# display_v1.net
KiCad netlist of a schematic drawn in EAGLE
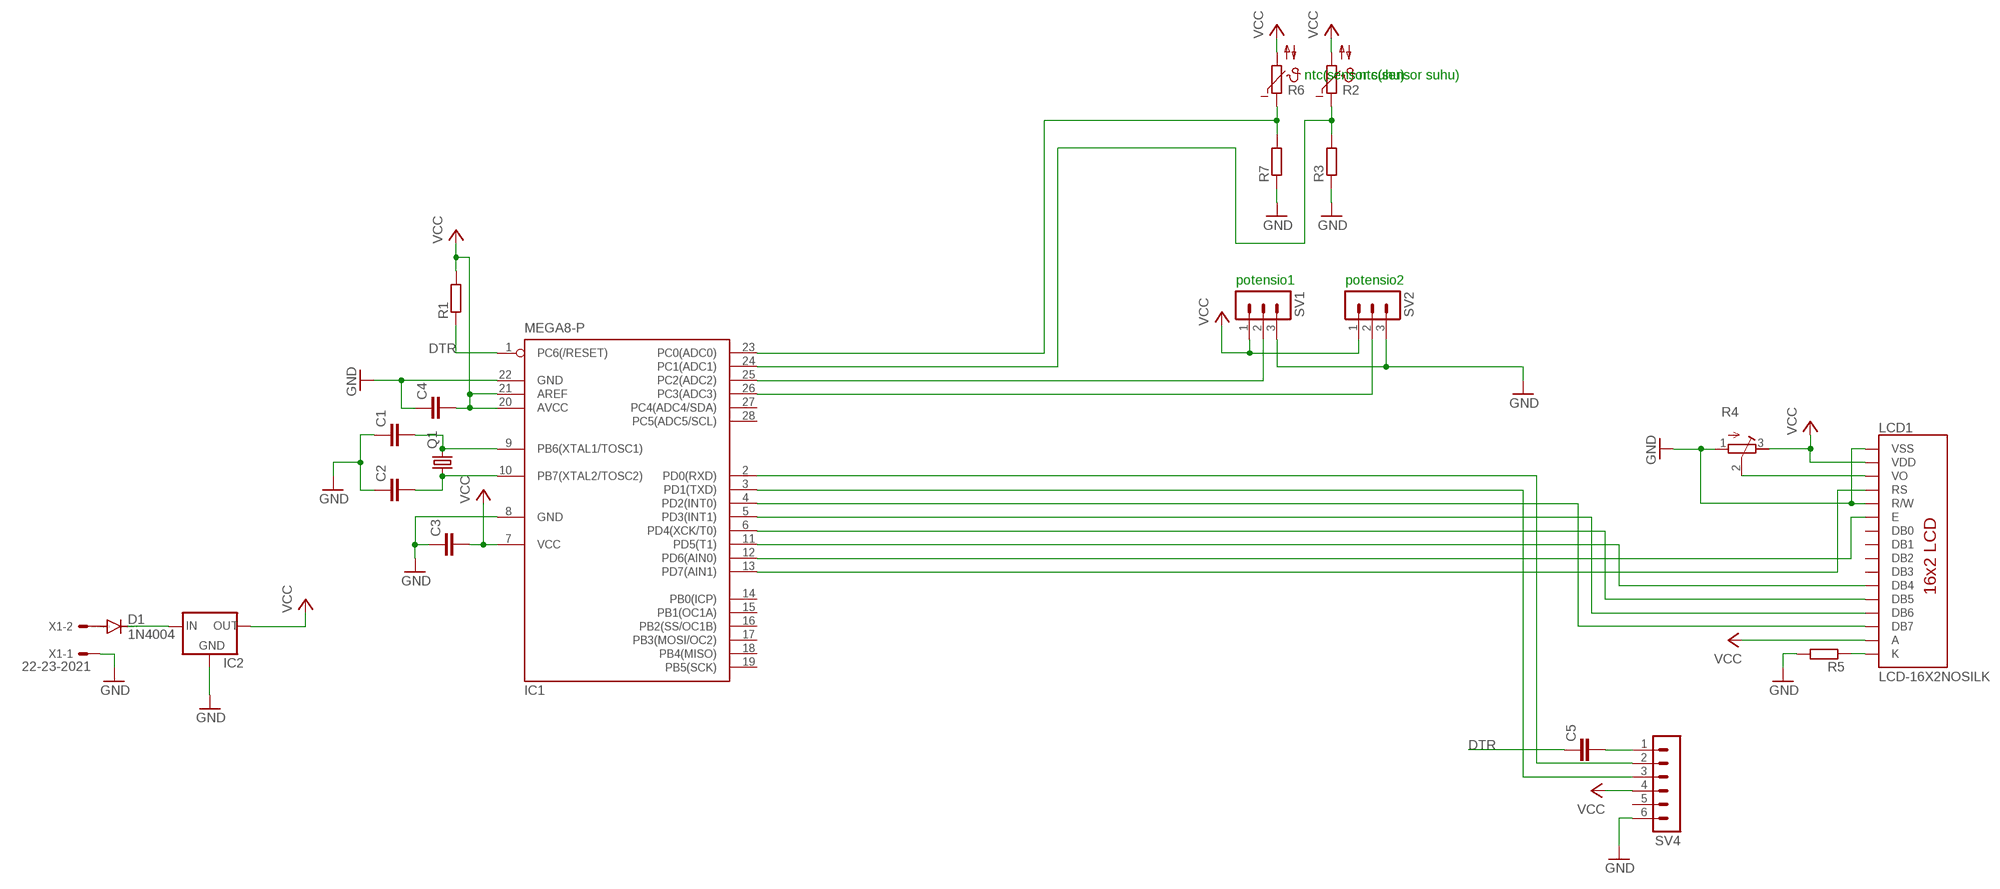
[diagram p0: schematic, sheet 1]

(export (version "E")
  (design (tool "Eeschema 10.0.6"))
  (components
    (comp (ref "C1")
      (value "C-EU025-025X050")
      (footprint "eagle-import:C025-025X050")
      (libsource (lib "eagle-import") (part "C-EU025-025X050"))
    )
    (comp (ref "C2")
      (value "C-EU025-025X050")
      (footprint "eagle-import:C025-025X050")
      (libsource (lib "eagle-import") (part "C-EU025-025X050"))
    )
    (comp (ref "C3")
      (value "C-EU050-025X075")
      (footprint "eagle-import:C050-025X075")
      (libsource (lib "eagle-import") (part "C-EU050-025X075"))
    )
    (comp (ref "C4")
      (value "C-EU050-025X075")
      (footprint "eagle-import:C050-025X075")
      (libsource (lib "eagle-import") (part "C-EU050-025X075"))
    )
    (comp (ref "C5")
      (value "C-EU050-025X075")
      (footprint "eagle-import:C050-025X075")
      (libsource (lib "eagle-import") (part "C-EU050-025X075"))
    )
    (comp (ref "D1")
      (value "1N4004")
      (footprint "eagle-import:DO41-10")
      (libsource (lib "eagle-import") (part "1N4004"))
    )
    (comp (ref "IC1")
      (value "MEGA8-P")
      (footprint "eagle-import:DIL28-3")
      (libsource (lib "eagle-import") (part "MEGA8-P"))
    )
    (comp (ref "IC2")
      (value "78XXL")
      (footprint "eagle-import:78XXL")
      (libsource (lib "eagle-import") (part "78XXL"))
    )
    (comp (ref "LCD1")
      (value "LCD-16X2NOSILK")
      (footprint "eagle-import:LCD-16X2_NOSILK")
      (libsource (lib "eagle-import") (part "LCD-16X2NOSILK"))
    )
    (comp (ref "Q1")
      (value "CRYSTALHC49S")
      (footprint "eagle-import:HC49_S")
      (libsource (lib "eagle-import") (part "CRYSTALHC49S"))
    )
    (comp (ref "R1")
      (value "R-EU_0204/7")
      (footprint "eagle-import:0204_7")
      (libsource (lib "eagle-import") (part "R-EU_0204/7"))
    )
    (comp (ref "R2")
      (value "NTC642-6")
      (footprint "eagle-import:P642")
      (libsource (lib "eagle-import") (part "NTC642-6"))
    )
    (comp (ref "R3")
      (value "R-EU_0204/7")
      (footprint "eagle-import:0204_7")
      (libsource (lib "eagle-import") (part "R-EU_0204/7"))
    )
    (comp (ref "R4")
      (value "R-TRIMM64W")
      (footprint "eagle-import:RTRIM64W")
      (libsource (lib "eagle-import") (part "R-TRIMM64W"))
    )
    (comp (ref "R5")
      (value "R-EU_0204/7")
      (footprint "eagle-import:0204_7")
      (libsource (lib "eagle-import") (part "R-EU_0204/7"))
    )
    (comp (ref "R6")
      (value "NTC642-6")
      (footprint "eagle-import:P642")
      (libsource (lib "eagle-import") (part "NTC642-6"))
    )
    (comp (ref "R7")
      (value "R-EU_0204/7")
      (footprint "eagle-import:0204_7")
      (libsource (lib "eagle-import") (part "R-EU_0204/7"))
    )
    (comp (ref "SV1")
      (value "MA03-1")
      (footprint "eagle-import:MA03-1")
      (libsource (lib "eagle-import") (part "MA03-1"))
    )
    (comp (ref "SV2")
      (value "MA03-1")
      (footprint "eagle-import:MA03-1")
      (libsource (lib "eagle-import") (part "MA03-1"))
    )
    (comp (ref "SV4")
      (value "MA06-1")
      (footprint "eagle-import:MA06-1")
      (libsource (lib "eagle-import") (part "MA06-1"))
    )
    (comp (ref "X1")
      (value "22-23-2021")
      (footprint "eagle-import:22-23-2021")
      (fields (field (name "MF") "MOLEX"))
      (libsource (lib "eagle-import") (part "22-23-2021"))
    )
  )
  (nets
    (net (code "1") (name "/DTR") (class "Default")
      (node (ref "C5") (pin "1") (pinfunction "1_1") (pintype "passive"))
      (node (ref "IC1") (pin "1") (pinfunction "PC6(/RESET)_1") (pintype "bidirectional"))
      (node (ref "R1") (pin "1") (pinfunction "1_1") (pintype "passive"))
    )
    (net (code "2") (name "GND") (class "Default")
      (node (ref "C1") (pin "1") (pinfunction "1_1") (pintype "passive"))
      (node (ref "C2") (pin "1") (pinfunction "1_1") (pintype "passive"))
      (node (ref "C3") (pin "1") (pinfunction "1_1") (pintype "passive"))
      (node (ref "C4") (pin "1") (pinfunction "1_1") (pintype "passive"))
      (node (ref "IC1") (pin "22") (pinfunction "GND_22") (pintype "power_in"))
      (node (ref "IC1") (pin "8") (pinfunction "GND_8") (pintype "power_in"))
      (node (ref "IC2") (pin "GND") (pinfunction "GND_GND") (pintype "input"))
      (node (ref "LCD1") (pin "1") (pinfunction "VSS_1") (pintype "power_in"))
      (node (ref "LCD1") (pin "5") (pinfunction "R/W_5") (pintype "input"))
      (node (ref "R3") (pin "1") (pinfunction "1_1") (pintype "passive"))
      (node (ref "R4") (pin "1") (pinfunction "A_1") (pintype "passive"))
      (node (ref "R5") (pin "2") (pinfunction "2_2") (pintype "passive"))
      (node (ref "R7") (pin "1") (pinfunction "1_1") (pintype "passive"))
      (node (ref "SV1") (pin "3") (pinfunction "3_3") (pintype "passive"))
      (node (ref "SV2") (pin "3") (pinfunction "3_3") (pintype "passive"))
      (node (ref "SV4") (pin "6") (pinfunction "6_6") (pintype "passive"))
      (node (ref "X1") (pin "1") (pinfunction "S_1") (pintype "passive"))
    )
    (net (code "3") (name "Net-(C5-Pad2)") (class "Default")
      (node (ref "C5") (pin "2") (pinfunction "2_2") (pintype "passive"))
      (node (ref "SV4") (pin "1") (pinfunction "1_1") (pintype "passive"))
    )
    (net (code "4") (name "Net-(D1-PadC)") (class "Default")
      (node (ref "D1") (pin "C") (pinfunction "C_C") (pintype "passive"))
      (node (ref "IC2") (pin "IN") (pinfunction "IN_IN") (pintype "input"))
    )
    (net (code "5") (name "Net-(IC1-PB6(XTAL1{slash}TOSC1))") (class "Default")
      (node (ref "C1") (pin "2") (pinfunction "2_2") (pintype "passive"))
      (node (ref "IC1") (pin "9") (pinfunction "PB6(XTAL1/TOSC1)_9") (pintype "bidirectional"))
      (node (ref "Q1") (pin "2") (pinfunction "2_2") (pintype "passive"))
    )
    (net (code "6") (name "Net-(IC1-PB7(XTAL2{slash}TOSC2))") (class "Default")
      (node (ref "C2") (pin "2") (pinfunction "2_2") (pintype "passive"))
      (node (ref "IC1") (pin "10") (pinfunction "PB7(XTAL2/TOSC2)_10") (pintype "bidirectional"))
      (node (ref "Q1") (pin "1") (pinfunction "1_1") (pintype "passive"))
    )
    (net (code "7") (name "Net-(IC1-PC0(ADC0))") (class "Default")
      (node (ref "IC1") (pin "23") (pinfunction "PC0(ADC0)_23") (pintype "bidirectional"))
      (node (ref "R6") (pin "1") (pinfunction "1_1") (pintype "passive"))
      (node (ref "R7") (pin "2") (pinfunction "2_2") (pintype "passive"))
    )
    (net (code "8") (name "Net-(IC1-PC1(ADC1))") (class "Default")
      (node (ref "IC1") (pin "24") (pinfunction "PC1(ADC1)_24") (pintype "bidirectional"))
      (node (ref "R2") (pin "1") (pinfunction "1_1") (pintype "passive"))
      (node (ref "R3") (pin "2") (pinfunction "2_2") (pintype "passive"))
    )
    (net (code "9") (name "Net-(IC1-PC2(ADC2))") (class "Default")
      (node (ref "IC1") (pin "25") (pinfunction "PC2(ADC2)_25") (pintype "bidirectional"))
      (node (ref "SV1") (pin "2") (pinfunction "2_2") (pintype "passive"))
    )
    (net (code "10") (name "Net-(IC1-PC3(ADC3))") (class "Default")
      (node (ref "IC1") (pin "26") (pinfunction "PC3(ADC3)_26") (pintype "bidirectional"))
      (node (ref "SV2") (pin "2") (pinfunction "2_2") (pintype "passive"))
    )
    (net (code "11") (name "Net-(IC1-PD0(RXD))") (class "Default")
      (node (ref "IC1") (pin "2") (pinfunction "PD0(RXD)_2") (pintype "bidirectional"))
      (node (ref "SV4") (pin "2") (pinfunction "2_2") (pintype "passive"))
    )
    (net (code "12") (name "Net-(IC1-PD1(TXD))") (class "Default")
      (node (ref "IC1") (pin "3") (pinfunction "PD1(TXD)_3") (pintype "bidirectional"))
      (node (ref "SV4") (pin "3") (pinfunction "3_3") (pintype "passive"))
    )
    (net (code "13") (name "Net-(IC1-PD2(INT0))") (class "Default")
      (node (ref "IC1") (pin "4") (pinfunction "PD2(INT0)_4") (pintype "bidirectional"))
      (node (ref "LCD1") (pin "14") (pinfunction "DB7_14") (pintype "bidirectional"))
    )
    (net (code "14") (name "Net-(IC1-PD3(INT1))") (class "Default")
      (node (ref "IC1") (pin "5") (pinfunction "PD3(INT1)_5") (pintype "bidirectional"))
      (node (ref "LCD1") (pin "13") (pinfunction "DB6_13") (pintype "bidirectional"))
    )
    (net (code "15") (name "Net-(IC1-PD4(XCK{slash}T0))") (class "Default")
      (node (ref "IC1") (pin "6") (pinfunction "PD4(XCK/T0)_6") (pintype "bidirectional"))
      (node (ref "LCD1") (pin "12") (pinfunction "DB5_12") (pintype "bidirectional"))
    )
    (net (code "16") (name "Net-(IC1-PD5(T1))") (class "Default")
      (node (ref "IC1") (pin "11") (pinfunction "PD5(T1)_11") (pintype "bidirectional"))
      (node (ref "LCD1") (pin "11") (pinfunction "DB4_11") (pintype "bidirectional"))
    )
    (net (code "17") (name "Net-(IC1-PD6(AIN0))") (class "Default")
      (node (ref "IC1") (pin "12") (pinfunction "PD6(AIN0)_12") (pintype "bidirectional"))
      (node (ref "LCD1") (pin "6") (pinfunction "E_6") (pintype "input"))
    )
    (net (code "18") (name "Net-(IC1-PD7(AIN1))") (class "Default")
      (node (ref "IC1") (pin "13") (pinfunction "PD7(AIN1)_13") (pintype "bidirectional"))
      (node (ref "LCD1") (pin "4") (pinfunction "RS_4") (pintype "input"))
    )
    (net (code "19") (name "Net-(LCD1-K)") (class "Default")
      (node (ref "LCD1") (pin "16") (pinfunction "K_16") (pintype "power_in"))
      (node (ref "R5") (pin "1") (pinfunction "1_1") (pintype "passive"))
    )
    (net (code "20") (name "Net-(LCD1-VO)") (class "Default")
      (node (ref "LCD1") (pin "3") (pinfunction "VO_3") (pintype "bidirectional"))
      (node (ref "R4") (pin "2") (pinfunction "S_2") (pintype "passive"))
    )
    (net (code "21") (name "Net-(X1B-S)") (class "Default")
      (node (ref "D1") (pin "A") (pinfunction "A_A") (pintype "passive"))
      (node (ref "X1") (pin "2") (pinfunction "S_2") (pintype "passive"))
    )
    (net (code "22") (name "VCC") (class "Default")
      (node (ref "C3") (pin "2") (pinfunction "2_2") (pintype "passive"))
      (node (ref "C4") (pin "2") (pinfunction "2_2") (pintype "passive"))
      (node (ref "IC1") (pin "20") (pinfunction "AVCC_20") (pintype "power_in"))
      (node (ref "IC1") (pin "21") (pinfunction "AREF_21") (pintype "passive"))
      (node (ref "IC1") (pin "7") (pinfunction "VCC_7") (pintype "power_in"))
      (node (ref "IC2") (pin "OUT") (pinfunction "OUT_OUT") (pintype "passive"))
      (node (ref "LCD1") (pin "15") (pinfunction "A_15") (pintype "power_in"))
      (node (ref "LCD1") (pin "2") (pinfunction "VDD_2") (pintype "power_in"))
      (node (ref "R1") (pin "2") (pinfunction "2_2") (pintype "passive"))
      (node (ref "R2") (pin "2") (pinfunction "2_2") (pintype "passive"))
      (node (ref "R4") (pin "3") (pinfunction "E_3") (pintype "passive"))
      (node (ref "R6") (pin "2") (pinfunction "2_2") (pintype "passive"))
      (node (ref "SV1") (pin "1") (pinfunction "1_1") (pintype "passive"))
      (node (ref "SV2") (pin "1") (pinfunction "1_1") (pintype "passive"))
      (node (ref "SV4") (pin "4") (pinfunction "4_4") (pintype "passive"))
    )
    (net (code "23") (name "unconnected-(IC1-PB0(ICP)-Pad14)") (class "Default")
      (node (ref "IC1") (pin "14") (pinfunction "PB0(ICP)_14") (pintype "bidirectional"))
    )
    (net (code "24") (name "unconnected-(IC1-PB1(OC1A)-Pad15)") (class "Default")
      (node (ref "IC1") (pin "15") (pinfunction "PB1(OC1A)_15") (pintype "bidirectional"))
    )
    (net (code "25") (name "unconnected-(IC1-PB2(SS{slash}OC1B)-Pad16)") (class "Default")
      (node (ref "IC1") (pin "16") (pinfunction "PB2(SS/OC1B)_16") (pintype "bidirectional"))
    )
    (net (code "26") (name "unconnected-(IC1-PB3(MOSI{slash}OC2)-Pad17)") (class "Default")
      (node (ref "IC1") (pin "17") (pinfunction "PB3(MOSI/OC2)_17") (pintype "bidirectional"))
    )
    (net (code "27") (name "unconnected-(IC1-PB4(MISO)-Pad18)") (class "Default")
      (node (ref "IC1") (pin "18") (pinfunction "PB4(MISO)_18") (pintype "bidirectional"))
    )
    (net (code "28") (name "unconnected-(IC1-PB5(SCK)-Pad19)") (class "Default")
      (node (ref "IC1") (pin "19") (pinfunction "PB5(SCK)_19") (pintype "bidirectional"))
    )
    (net (code "29") (name "unconnected-(IC1-PC4(ADC4{slash}SDA)-Pad27)") (class "Default")
      (node (ref "IC1") (pin "27") (pinfunction "PC4(ADC4/SDA)_27") (pintype "bidirectional"))
    )
    (net (code "30") (name "unconnected-(IC1-PC5(ADC5{slash}SCL)-Pad28)") (class "Default")
      (node (ref "IC1") (pin "28") (pinfunction "PC5(ADC5/SCL)_28") (pintype "bidirectional"))
    )
    (net (code "31") (name "unconnected-(LCD1-DB0-Pad7)") (class "Default")
      (node (ref "LCD1") (pin "7") (pinfunction "DB0_7") (pintype "bidirectional"))
    )
    (net (code "32") (name "unconnected-(LCD1-DB1-Pad8)") (class "Default")
      (node (ref "LCD1") (pin "8") (pinfunction "DB1_8") (pintype "bidirectional"))
    )
    (net (code "33") (name "unconnected-(LCD1-DB2-Pad9)") (class "Default")
      (node (ref "LCD1") (pin "9") (pinfunction "DB2_9") (pintype "bidirectional"))
    )
    (net (code "34") (name "unconnected-(LCD1-DB3-Pad10)") (class "Default")
      (node (ref "LCD1") (pin "10") (pinfunction "DB3_10") (pintype "bidirectional"))
    )
    (net (code "35") (name "unconnected-(SV4-Pad5)") (class "Default")
      (node (ref "SV4") (pin "5") (pinfunction "5_5") (pintype "passive"))
    )
  )
)
